# USB_Downstream_Type_C_Port_2.net
KiCad netlist of a schematic drawn in Altium Designer
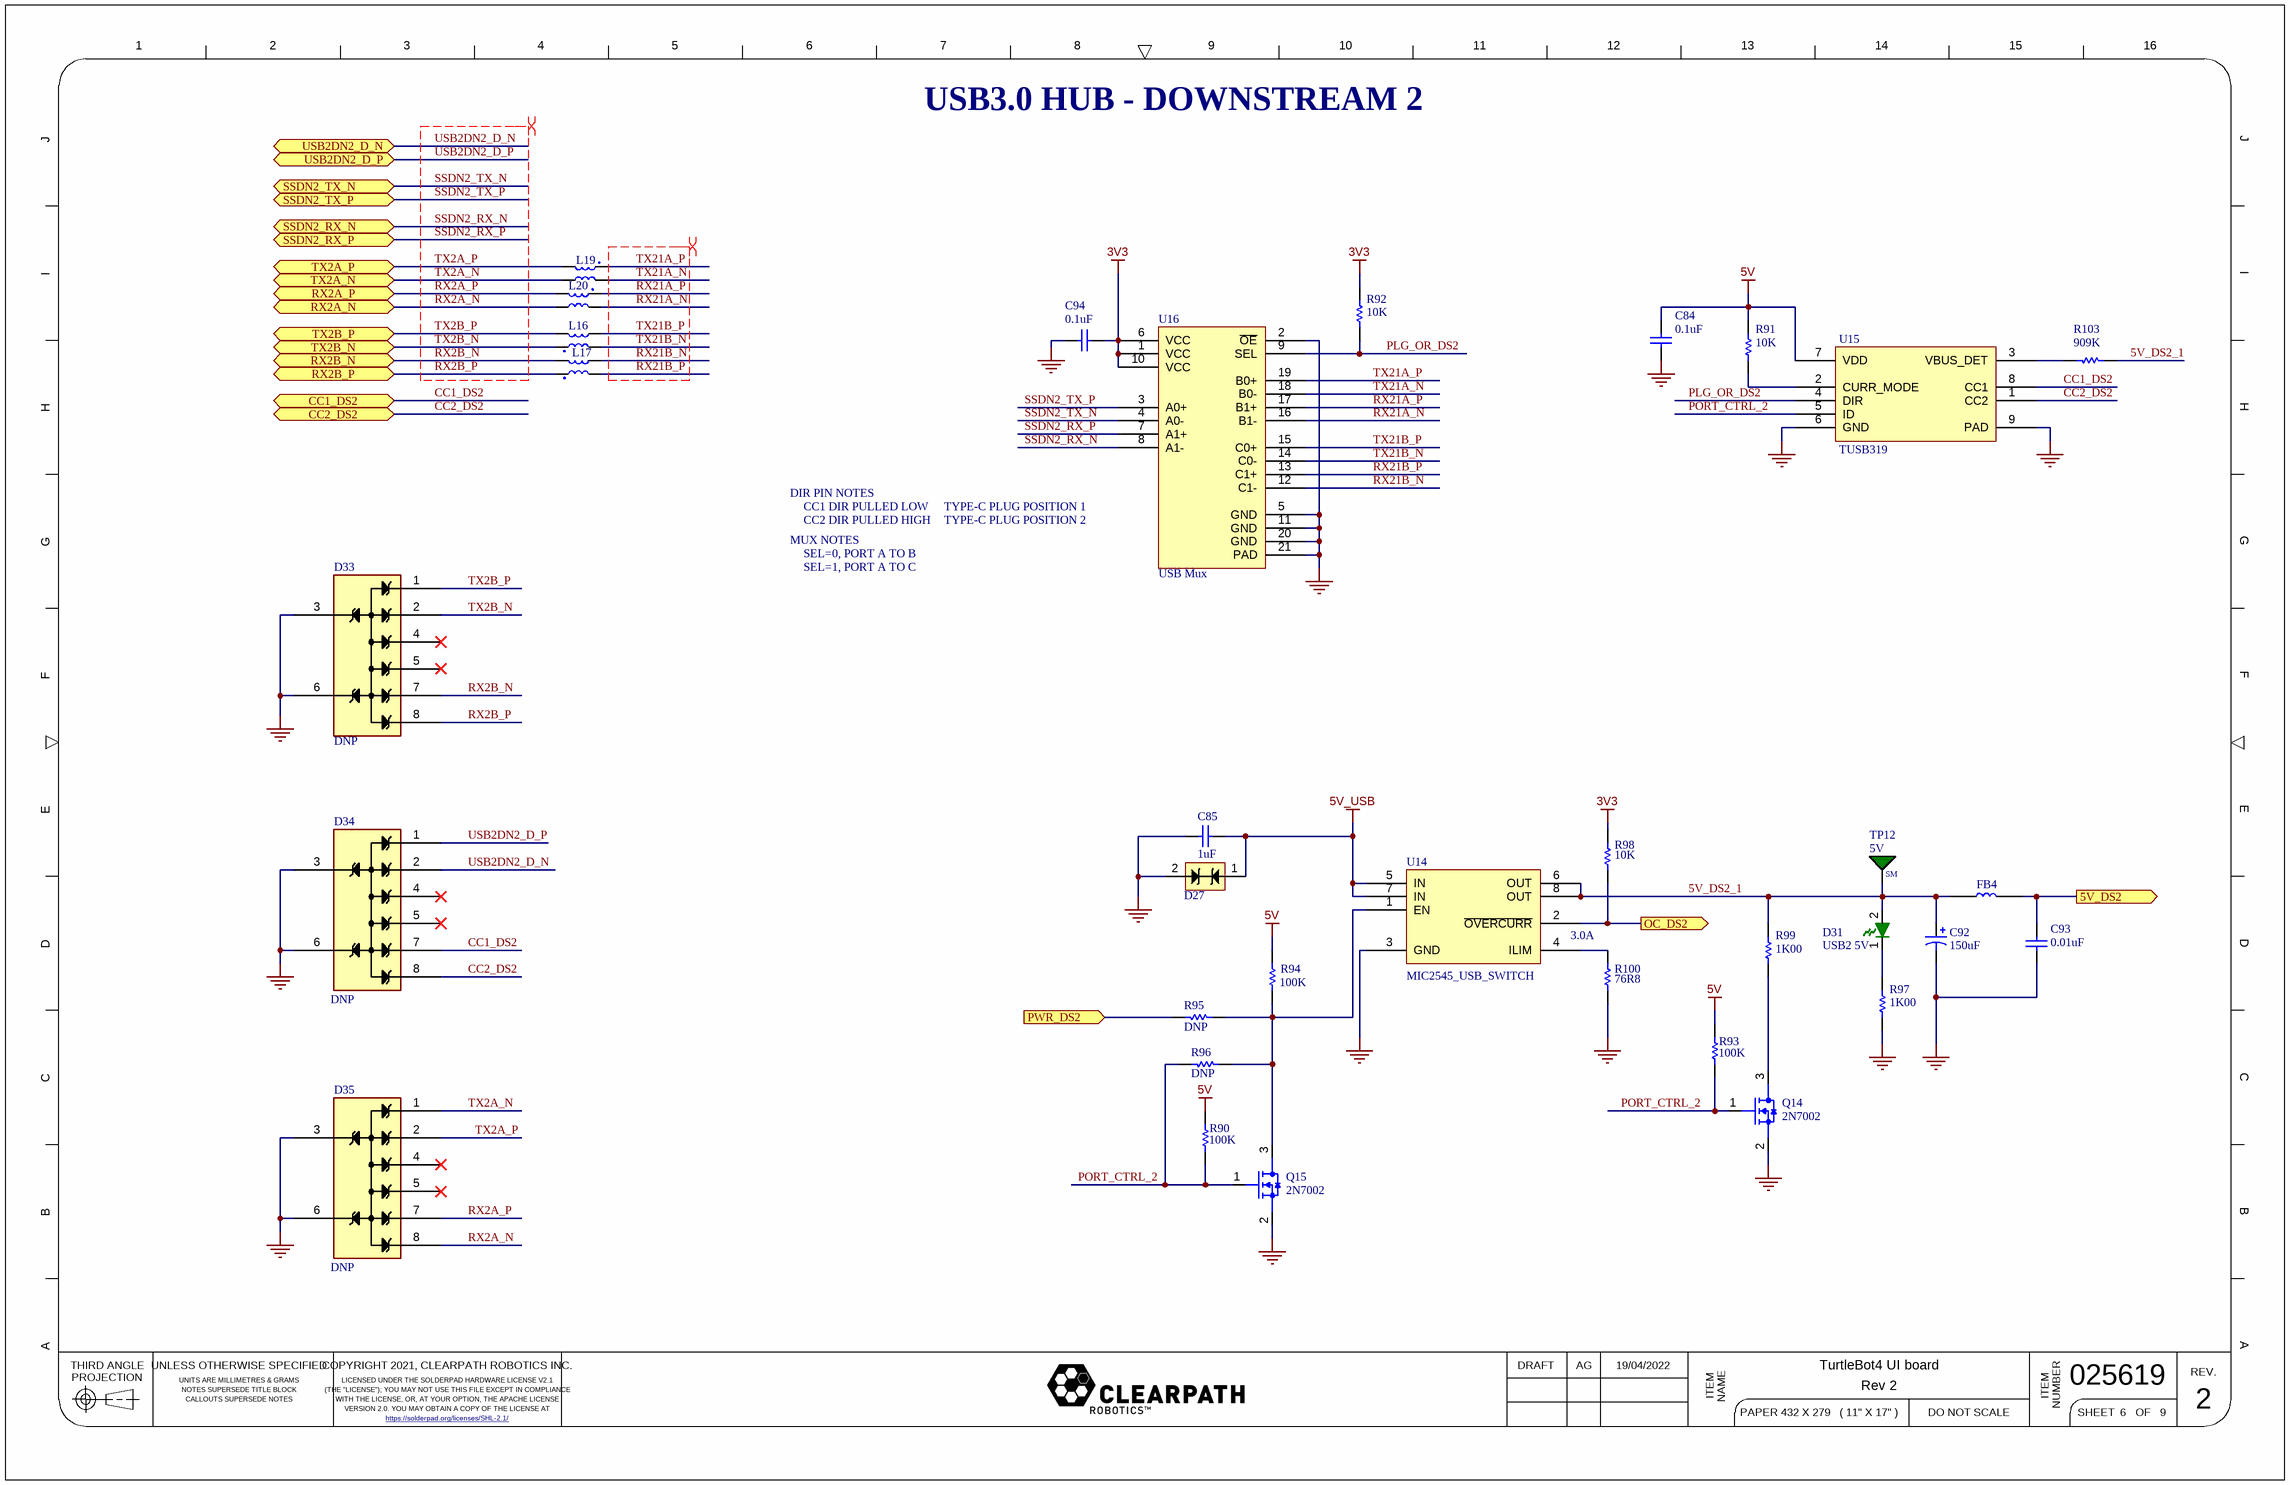
[diagram p0: USB Downstream Type C Port 2.SchDoc]

(export (version "E")
  (design (tool "Eeschema 10.0.6"))
  (components
    (comp (ref "C84")
      (value "0.1uF")
      (footprint "C0805")
      (description "Capacitor")
      (fields (field (name "TOLERANCE") "10%") (field (name "VOLTAGE") "50V"))
      (libsource (lib "CPR_CommonDevices") (part "Capacitor _SMT"))
    )
    (comp (ref "C85")
      (value "1uF")
      (footprint "C0805")
      (description "Capacitor")
      (fields (field (name "TOLERANCE") "-20 +80") (field (name "VOLTAGE") "50V"))
      (libsource (lib "CPR_CommonDevices") (part "Capacitor _SMT"))
    )
    (comp (ref "C92")
      (value "150uF")
      (footprint "T494D157K016AT:CAPMP7.6X4.3_3.1N_KEM-M")
      (description "CAP TANT 150UF 10% 16V 2917")
      (fields (field (name "VOLTAGE") "16V") (field (name "TOLERANCE") "10%"))
      (libsource (lib "Miscellaneous Devices") (part "Cap Pol1"))
    )
    (comp (ref "C93")
      (value "0.01uF")
      (footprint "C0805")
      (description "Capacitor")
      (fields (field (name "TOLERANCE") "10%") (field (name "VOLTAGE") "50V"))
      (libsource (lib "CPR_CommonDevices") (part "Capacitor _SMT"))
    )
    (comp (ref "C94")
      (value "0.1uF")
      (footprint "C0805")
      (description "Capacitor")
      (fields (field (name "TOLERANCE") "10%") (field (name "VOLTAGE") "50V"))
      (libsource (lib "CPR_CommonDevices") (part "Capacitor _SMT"))
    )
    (comp (ref "D27")
      (value "TVS DIODE BIDIR 15V SMC")
      (footprint "General PCB Library:DO-214AA")
      (description "TVS 600W 15V BI-DIR DO-214AA")
      (fields (field (name "MFG") "Littelfuse Inc."))
      (libsource (lib "SMBJ15CA") (part "TVS DIODE BIDIR 15V SMC"))
    )
    (comp (ref "D31")
      (value "USB2 5V")
      (footprint "LED_0805_GRN")
      (description "Green LED")
      (fields (field (name "MFG") "LiteOn"))
      (libsource (lib "Green LED") (part "GREEN_LED"))
    )
    (comp (ref "D33")
      (value "DNP")
      (footprint "ESD7016")
      (description "USB3 TVS diode assy")
      (fields (field (name "MFG") "ON Semi"))
      (libsource (lib "ONSemi_ESD7016") (part "ESD7016"))
    )
    (comp (ref "D34")
      (value "DNP")
      (footprint "ESD7016")
      (description "USB3 TVS diode assy")
      (fields (field (name "MFG") "ON Semi"))
      (libsource (lib "ONSemi_ESD7016") (part "ESD7016"))
    )
    (comp (ref "D35")
      (value "DNP")
      (footprint "ESD7016")
      (description "USB3 TVS diode assy")
      (fields (field (name "MFG") "ON Semi"))
      (libsource (lib "ONSemi_ESD7016") (part "ESD7016"))
    )
    (comp (ref "FB4")
      (value "742792602")
      (footprint "General PCB Library:R0603")
      (description "60 Ohms 1 Signal Line Ferrite Bead 0603 (1608 Metric) 3A 40mOhm")
      (libsource (lib "742792602") (part "742792602"))
    )
    (comp (ref "L16")
      (value "CMC 100MA 2LN 90 OHM SMD2")
      (footprint "cmc_90_ohms:cmc_90_ohms")
      (description "Line Common Mode Choke Surface Mount 90 Ohms 100mA DCR 5Ohm")
      (libsource (lib "cmc_90_ohms") (part "CMC 90_Ohms"))
    )
    (comp (ref "L17")
      (value "CMC 100MA 2LN 90 OHM SMD2")
      (footprint "cmc_90_ohms:cmc_90_ohms")
      (description "Line Common Mode Choke Surface Mount 90 Ohms 100mA DCR 5Ohm")
      (libsource (lib "cmc_90_ohms") (part "CMC 90_Ohms"))
    )
    (comp (ref "L19")
      (value "CMC 100MA 2LN 90 OHM SMD2")
      (footprint "cmc_90_ohms:cmc_90_ohms")
      (description "Line Common Mode Choke Surface Mount 90 Ohms 100mA DCR 5Ohm")
      (libsource (lib "cmc_90_ohms") (part "CMC 90_Ohms"))
    )
    (comp (ref "L20")
      (value "CMC 100MA 2LN 90 OHM SMD2")
      (footprint "cmc_90_ohms:cmc_90_ohms")
      (description "Line Common Mode Choke Surface Mount 90 Ohms 100mA DCR 5Ohm")
      (libsource (lib "cmc_90_ohms") (part "CMC 90_Ohms"))
    )
    (comp (ref "Q14")
      (value "NFET")
      (footprint "SOT-23-3")
      (fields (field (name "MFG PN") "2N7002") (field (name "MFG") "ON Semi"))
      (libsource (lib "NFET_SINGLE") (part "NFET_SNGL"))
    )
    (comp (ref "Q15")
      (value "NFET")
      (footprint "SOT-23-3")
      (fields (field (name "MFG PN") "2N7002") (field (name "MFG") "ON Semi"))
      (libsource (lib "NFET_SINGLE") (part "NFET_SNGL"))
    )
    (comp (ref "R90")
      (value "100K")
      (footprint "R0805")
      (description "Resistor")
      (fields (field (name "TOLERANCE") "1%") (field (name "MFG") "Yageo"))
      (libsource (lib "") (part "Resistor_SMT_1"))
    )
    (comp (ref "R91")
      (value "10K")
      (footprint "R0805")
      (description "Resistor")
      (fields (field (name "TOLERANCE") "1%") (field (name "MFG") "Yageo"))
      (libsource (lib "") (part "Resistor_SMT_1"))
    )
    (comp (ref "R92")
      (value "10K")
      (footprint "R0805")
      (description "Resistor")
      (fields (field (name "TOLERANCE") "1%") (field (name "MFG") "Yageo"))
      (libsource (lib "") (part "Resistor_SMT_1"))
    )
    (comp (ref "R93")
      (value "100K")
      (footprint "R0805")
      (description "Resistor")
      (fields (field (name "TOLERANCE") "1%") (field (name "MFG") "Yageo"))
      (libsource (lib "") (part "Resistor_SMT_1"))
    )
    (comp (ref "R94")
      (value "100K")
      (footprint "R0805")
      (description "Resistor")
      (fields (field (name "TOLERANCE") "1%") (field (name "MFG") "Yageo"))
      (libsource (lib "") (part "Resistor_SMT_1"))
    )
    (comp (ref "R95")
      (value "DNP")
      (footprint "R0805")
      (description "Resistor")
      (fields (field (name "MFG") "Yageo") (field (name "Comment") "Resistor_SMT"))
      (libsource (lib "CPR_CommonDevices") (part "Resistor_SMT"))
    )
    (comp (ref "R96")
      (value "DNP")
      (footprint "R0805")
      (description "Resistor")
      (fields (field (name "MFG") "Yageo") (field (name "Comment") "Resistor_SMT"))
      (libsource (lib "CPR_CommonDevices") (part "Resistor_SMT"))
    )
    (comp (ref "R97")
      (value "1K00")
      (footprint "R0805")
      (description "Resistor")
      (fields (field (name "TOLERANCE") "1%") (field (name "MFG") "Yageo"))
      (libsource (lib "") (part "Resistor_SMT_1"))
    )
    (comp (ref "R98")
      (value "10K")
      (footprint "R0805")
      (description "Resistor")
      (fields (field (name "TOLERANCE") "1%") (field (name "MFG") "Yageo"))
      (libsource (lib "") (part "Resistor_SMT_1"))
    )
    (comp (ref "R99")
      (value "1K00")
      (footprint "R0805")
      (description "Resistor")
      (fields (field (name "TOLERANCE") "1%") (field (name "MFG") "Yageo"))
      (libsource (lib "") (part "Resistor_SMT_1"))
    )
    (comp (ref "R100")
      (value "3.0A")
      (footprint "R0805")
      (description "Resistor")
      (fields
        (field (name "ALTIUM_VALUE") "76R8")
        (field (name "TOLERANCE") "1%")
        (field (name "MFG") "Yageo")
      )
      (libsource (lib "") (part "Resistor_SMT_1"))
    )
    (comp (ref "R103")
      (value "909K")
      (footprint "R0805")
      (description "Resistor")
      (fields (field (name "TOLERANCE") "1%") (field (name "MFG") "Yageo"))
      (libsource (lib "") (part "Resistor_SMT_1"))
    )
    (comp (ref "TP12")
      (value "5V")
      (footprint "TP_28SM")
      (description "Test point, 28 Mil exposed pad")
      (fields (field (name "MANUFACTURER") "Clearpath Robotics Inc."))
      (libsource (lib "Test Points") (part "TP_28SM"))
    )
    (comp (ref "U14")
      (value "MIC2545_USB_SWITCH")
      (footprint "SOIC-8-150")
      (description "IC PWR SWITCH N-CHAN 1:1 8SOIC")
      (fields (field (name "MFG") "Microchip"))
      (libsource (lib "MIC2545") (part "MIC2545_USB_SWITCH"))
    )
    (comp (ref "U15")
      (value "TUSB319")
      (footprint "WSON8")
      (description "USB Type C Controller")
      (fields (field (name "MFG") "Texas Instruments"))
      (libsource (lib "TUSB319") (part "TUSB319"))
    )
    (comp (ref "U16")
      (value "USB Mux")
      (footprint "TQFN20")
      (description "TC7PCI3212MT,LF USB3.0 Mux")
      (fields (field (name "MANUFACTURER") "Toshiba"))
      (libsource (lib "TOSHIBA TC7PCI3212MT") (part "TC7PCI3212"))
    )
  )
  (nets
    (net (code "1") (name "/5V_DS2") (class "Default")
      (node (ref "C93") (pin "1") (pinfunction "1_1") (pintype "passive"))
      (node (ref "FB4") (pin "2") (pinfunction "2_2") (pintype "passive"))
    )
    (net (code "2") (name "/5V_DS2_1") (class "Default")
      (node (ref "C92") (pin "1") (pinfunction "1_1") (pintype "passive"))
      (node (ref "D31") (pin "2") (pinfunction "RA_2") (pintype "passive"))
      (node (ref "FB4") (pin "1") (pinfunction "1_1") (pintype "passive"))
      (node (ref "R103") (pin "2") (pinfunction "2_2") (pintype "passive"))
      (node (ref "R99") (pin "1") (pinfunction "1_1") (pintype "passive"))
      (node (ref "TP12") (pin "1") (pintype "passive"))
      (node (ref "U14") (pin "6") (pinfunction "OUT_6") (pintype "passive"))
      (node (ref "U14") (pin "8") (pinfunction "OUT_8") (pintype "passive"))
    )
    (net (code "3") (name "/CC1_DS2") (class "Default")
      (node (ref "D34") (pin "7") (pintype "passive"))
      (node (ref "U15") (pin "8") (pinfunction "CC1_8") (pintype "passive"))
    )
    (net (code "4") (name "/CC2_DS2") (class "Default")
      (node (ref "D34") (pin "8") (pintype "passive"))
      (node (ref "U15") (pin "1") (pinfunction "CC2_1") (pintype "passive"))
    )
    (net (code "5") (name "/OC_DS2") (class "Default")
      (node (ref "R98") (pin "2") (pinfunction "2_2") (pintype "passive"))
      (node (ref "U14") (pin "2") (pinfunction "~{OVERCURR}_2") (pintype "passive"))
    )
    (net (code "6") (name "/PLG_OR_DS2") (class "Default")
      (node (ref "R92") (pin "2") (pinfunction "2_2") (pintype "passive"))
      (node (ref "U15") (pin "4") (pinfunction "DIR_4") (pintype "passive"))
      (node (ref "U16") (pin "9") (pinfunction "SEL_9") (pintype "passive"))
    )
    (net (code "7") (name "/PORT_CTRL_2") (class "Default")
      (node (ref "Q14") (pin "1") (pinfunction "G1_1") (pintype "passive"))
      (node (ref "Q15") (pin "1") (pinfunction "G1_1") (pintype "passive"))
      (node (ref "R90") (pin "1") (pinfunction "1_1") (pintype "passive"))
      (node (ref "R93") (pin "1") (pinfunction "1_1") (pintype "passive"))
      (node (ref "R96") (pin "1") (pinfunction "1_1") (pintype "passive"))
      (node (ref "U15") (pin "5") (pinfunction "ID_5") (pintype "passive"))
    )
    (net (code "8") (name "/PWR_DS2") (class "Default")
      (node (ref "R95") (pin "1") (pinfunction "1_1") (pintype "passive"))
    )
    (net (code "9") (name "/RX2A_N") (class "Default")
      (node (ref "D35") (pin "8") (pintype "passive"))
      (node (ref "L20") (pin "3") (pinfunction "3_3") (pintype "passive"))
    )
    (net (code "10") (name "/RX2A_P") (class "Default")
      (node (ref "D35") (pin "7") (pintype "passive"))
      (node (ref "L20") (pin "4") (pinfunction "4_4") (pintype "passive"))
    )
    (net (code "11") (name "/RX2B_N") (class "Default")
      (node (ref "D33") (pin "7") (pintype "passive"))
      (node (ref "L17") (pin "2") (pinfunction "2_2") (pintype "passive"))
    )
    (net (code "12") (name "/RX2B_P") (class "Default")
      (node (ref "D33") (pin "8") (pintype "passive"))
      (node (ref "L17") (pin "1") (pinfunction "1_1") (pintype "passive"))
    )
    (net (code "13") (name "/RX21A_N") (class "Default")
      (node (ref "L20") (pin "2") (pinfunction "2_2") (pintype "passive"))
      (node (ref "U16") (pin "16") (pinfunction "B1-_16") (pintype "passive"))
    )
    (net (code "14") (name "/RX21A_P") (class "Default")
      (node (ref "L20") (pin "1") (pinfunction "1_1") (pintype "passive"))
      (node (ref "U16") (pin "17") (pinfunction "B1+_17") (pintype "passive"))
    )
    (net (code "15") (name "/RX21B_N") (class "Default")
      (node (ref "L17") (pin "3") (pinfunction "3_3") (pintype "passive"))
      (node (ref "U16") (pin "12") (pinfunction "C1-_12") (pintype "passive"))
    )
    (net (code "16") (name "/RX21B_P") (class "Default")
      (node (ref "L17") (pin "4") (pinfunction "4_4") (pintype "passive"))
      (node (ref "U16") (pin "13") (pinfunction "C1+_13") (pintype "passive"))
    )
    (net (code "17") (name "/SSDN2_RX_N") (class "Default")
      (node (ref "U16") (pin "8") (pinfunction "A1-_8") (pintype "passive"))
    )
    (net (code "18") (name "/SSDN2_RX_P") (class "Default")
      (node (ref "U16") (pin "7") (pinfunction "A1+_7") (pintype "passive"))
    )
    (net (code "19") (name "/SSDN2_TX_N") (class "Default")
      (node (ref "U16") (pin "4") (pinfunction "A0-_4") (pintype "passive"))
    )
    (net (code "20") (name "/SSDN2_TX_P") (class "Default")
      (node (ref "U16") (pin "3") (pinfunction "A0+_3") (pintype "passive"))
    )
    (net (code "21") (name "/TX2A_N") (class "Default")
      (node (ref "D35") (pin "1") (pinfunction "1_1") (pintype "passive"))
      (node (ref "L19") (pin "3") (pinfunction "3_3") (pintype "passive"))
    )
    (net (code "22") (name "/TX2A_P") (class "Default")
      (node (ref "D35") (pin "2") (pintype "passive"))
      (node (ref "L19") (pin "4") (pinfunction "4_4") (pintype "passive"))
    )
    (net (code "23") (name "/TX2B_N") (class "Default")
      (node (ref "D33") (pin "2") (pintype "passive"))
      (node (ref "L16") (pin "1") (pinfunction "1_1") (pintype "passive"))
    )
    (net (code "24") (name "/TX2B_P") (class "Default")
      (node (ref "D33") (pin "1") (pinfunction "1_1") (pintype "passive"))
      (node (ref "L16") (pin "2") (pinfunction "2_2") (pintype "passive"))
    )
    (net (code "25") (name "/TX21A_N") (class "Default")
      (node (ref "L19") (pin "2") (pinfunction "2_2") (pintype "passive"))
      (node (ref "U16") (pin "18") (pinfunction "B0-_18") (pintype "passive"))
    )
    (net (code "26") (name "/TX21A_P") (class "Default")
      (node (ref "L19") (pin "1") (pinfunction "1_1") (pintype "passive"))
      (node (ref "U16") (pin "19") (pinfunction "B0+_19") (pintype "passive"))
    )
    (net (code "27") (name "/TX21B_N") (class "Default")
      (node (ref "L16") (pin "4") (pinfunction "4_4") (pintype "passive"))
      (node (ref "U16") (pin "14") (pinfunction "C0-_14") (pintype "passive"))
    )
    (net (code "28") (name "/TX21B_P") (class "Default")
      (node (ref "L16") (pin "3") (pinfunction "3_3") (pintype "passive"))
      (node (ref "U16") (pin "15") (pinfunction "C0+_15") (pintype "passive"))
    )
    (net (code "29") (name "/USB2DN2_D_N") (class "Default") (node (ref "D34") (pin "2") (pintype "passive")))
    (net (code "30") (name "/USB2DN2_D_P") (class "Default")
      (node (ref "D34") (pin "1") (pinfunction "1_1") (pintype "passive"))
    )
    (net (code "31") (name "3V3") (class "Default")
      (node (ref "C94") (pin "1") (pinfunction "1_1") (pintype "passive"))
      (node (ref "R92") (pin "1") (pinfunction "1_1") (pintype "passive"))
      (node (ref "R98") (pin "1") (pinfunction "1_1") (pintype "passive"))
      (node (ref "U16") (pin "1") (pinfunction "VCC_1") (pintype "passive"))
      (node (ref "U16") (pin "10") (pinfunction "VCC_10") (pintype "passive"))
      (node (ref "U16") (pin "6") (pinfunction "VCC_6") (pintype "passive"))
    )
    (net (code "32") (name "5V") (class "Default")
      (node (ref "C84") (pin "1") (pinfunction "1_1") (pintype "passive"))
      (node (ref "R90") (pin "2") (pinfunction "2_2") (pintype "passive"))
      (node (ref "R91") (pin "1") (pinfunction "1_1") (pintype "passive"))
      (node (ref "R93") (pin "2") (pinfunction "2_2") (pintype "passive"))
      (node (ref "R94") (pin "2") (pinfunction "2_2") (pintype "passive"))
      (node (ref "U15") (pin "7") (pinfunction "VDD_7") (pintype "passive"))
    )
    (net (code "33") (name "5V_USB") (class "Default")
      (node (ref "C85") (pin "2") (pinfunction "2_2") (pintype "passive"))
      (node (ref "D27") (pin "1") (pintype "passive"))
      (node (ref "U14") (pin "5") (pinfunction "IN_5") (pintype "passive"))
      (node (ref "U14") (pin "7") (pinfunction "IN_7") (pintype "passive"))
    )
    (net (code "34") (name "GND") (class "Default")
      (node (ref "C84") (pin "2") (pinfunction "2_2") (pintype "passive"))
      (node (ref "C85") (pin "1") (pinfunction "1_1") (pintype "passive"))
      (node (ref "C92") (pin "2") (pinfunction "2_2") (pintype "passive"))
      (node (ref "C93") (pin "2") (pinfunction "2_2") (pintype "passive"))
      (node (ref "C94") (pin "2") (pinfunction "2_2") (pintype "passive"))
      (node (ref "D27") (pin "2") (pintype "passive"))
      (node (ref "D33") (pin "3") (pintype "passive"))
      (node (ref "D33") (pin "6") (pintype "passive"))
      (node (ref "D34") (pin "3") (pintype "passive"))
      (node (ref "D34") (pin "6") (pintype "passive"))
      (node (ref "D35") (pin "3") (pintype "passive"))
      (node (ref "D35") (pin "6") (pintype "passive"))
      (node (ref "Q14") (pin "2") (pinfunction "D1_2") (pintype "passive"))
      (node (ref "Q15") (pin "2") (pinfunction "D1_2") (pintype "passive"))
      (node (ref "R100") (pin "1") (pinfunction "1_1") (pintype "passive"))
      (node (ref "R97") (pin "2") (pinfunction "2_2") (pintype "passive"))
      (node (ref "U14") (pin "3") (pinfunction "GND_3") (pintype "passive"))
      (node (ref "U15") (pin "6") (pinfunction "GND_6") (pintype "passive"))
      (node (ref "U15") (pin "9") (pinfunction "PAD_9") (pintype "passive"))
      (node (ref "U16") (pin "11") (pinfunction "GND_11") (pintype "passive"))
      (node (ref "U16") (pin "2") (pinfunction "~{OE}_2") (pintype "passive"))
      (node (ref "U16") (pin "20") (pinfunction "GND_20") (pintype "passive"))
      (node (ref "U16") (pin "21") (pinfunction "PAD_21") (pintype "passive"))
      (node (ref "U16") (pin "5") (pinfunction "GND_5") (pintype "passive"))
    )
    (net (code "35") (name "Net-(D31-RK)") (class "Default")
      (node (ref "D31") (pin "1") (pinfunction "RK_1") (pintype "passive"))
      (node (ref "R97") (pin "1") (pinfunction "1_1") (pintype "passive"))
    )
    (net (code "36") (name "Net-(Q14-S1)") (class "Default")
      (node (ref "Q14") (pin "3") (pinfunction "S1_3") (pintype "passive"))
      (node (ref "R99") (pin "2") (pinfunction "2_2") (pintype "passive"))
    )
    (net (code "37") (name "Net-(Q15-S1)") (class "Default")
      (node (ref "Q15") (pin "3") (pinfunction "S1_3") (pintype "passive"))
      (node (ref "R94") (pin "1") (pinfunction "1_1") (pintype "passive"))
      (node (ref "R95") (pin "2") (pinfunction "2_2") (pintype "passive"))
      (node (ref "R96") (pin "2") (pinfunction "2_2") (pintype "passive"))
      (node (ref "U14") (pin "1") (pinfunction "EN_1") (pintype "passive"))
    )
    (net (code "38") (name "Net-(U14-ILIM)") (class "Default")
      (node (ref "R100") (pin "2") (pinfunction "2_2") (pintype "passive"))
      (node (ref "U14") (pin "4") (pinfunction "ILIM_4") (pintype "passive"))
    )
    (net (code "39") (name "Net-(U15-CURR_MODE)") (class "Default")
      (node (ref "R91") (pin "2") (pinfunction "2_2") (pintype "passive"))
      (node (ref "U15") (pin "2") (pinfunction "CURR_MODE_2") (pintype "passive"))
    )
    (net (code "40") (name "Net-(U15-VBUS_DET)") (class "Default")
      (node (ref "R103") (pin "1") (pinfunction "1_1") (pintype "passive"))
      (node (ref "U15") (pin "3") (pinfunction "VBUS_DET_3") (pintype "passive"))
    )
    (net (code "41") (name "unconnected-(D33-Pad4)") (class "Default")
      (node (ref "D33") (pin "4") (pintype "passive+no_connect"))
    )
    (net (code "42") (name "unconnected-(D33-Pad5)") (class "Default")
      (node (ref "D33") (pin "5") (pintype "passive+no_connect"))
    )
    (net (code "43") (name "unconnected-(D34-Pad4)") (class "Default")
      (node (ref "D34") (pin "4") (pintype "passive+no_connect"))
    )
    (net (code "44") (name "unconnected-(D34-Pad5)") (class "Default")
      (node (ref "D34") (pin "5") (pintype "passive+no_connect"))
    )
    (net (code "45") (name "unconnected-(D35-Pad4)") (class "Default")
      (node (ref "D35") (pin "4") (pintype "passive+no_connect"))
    )
    (net (code "46") (name "unconnected-(D35-Pad5)") (class "Default")
      (node (ref "D35") (pin "5") (pintype "passive+no_connect"))
    )
  )
)
